# Adafruit_MacroPad_2040.net
KiCad netlist of a schematic drawn in EAGLE
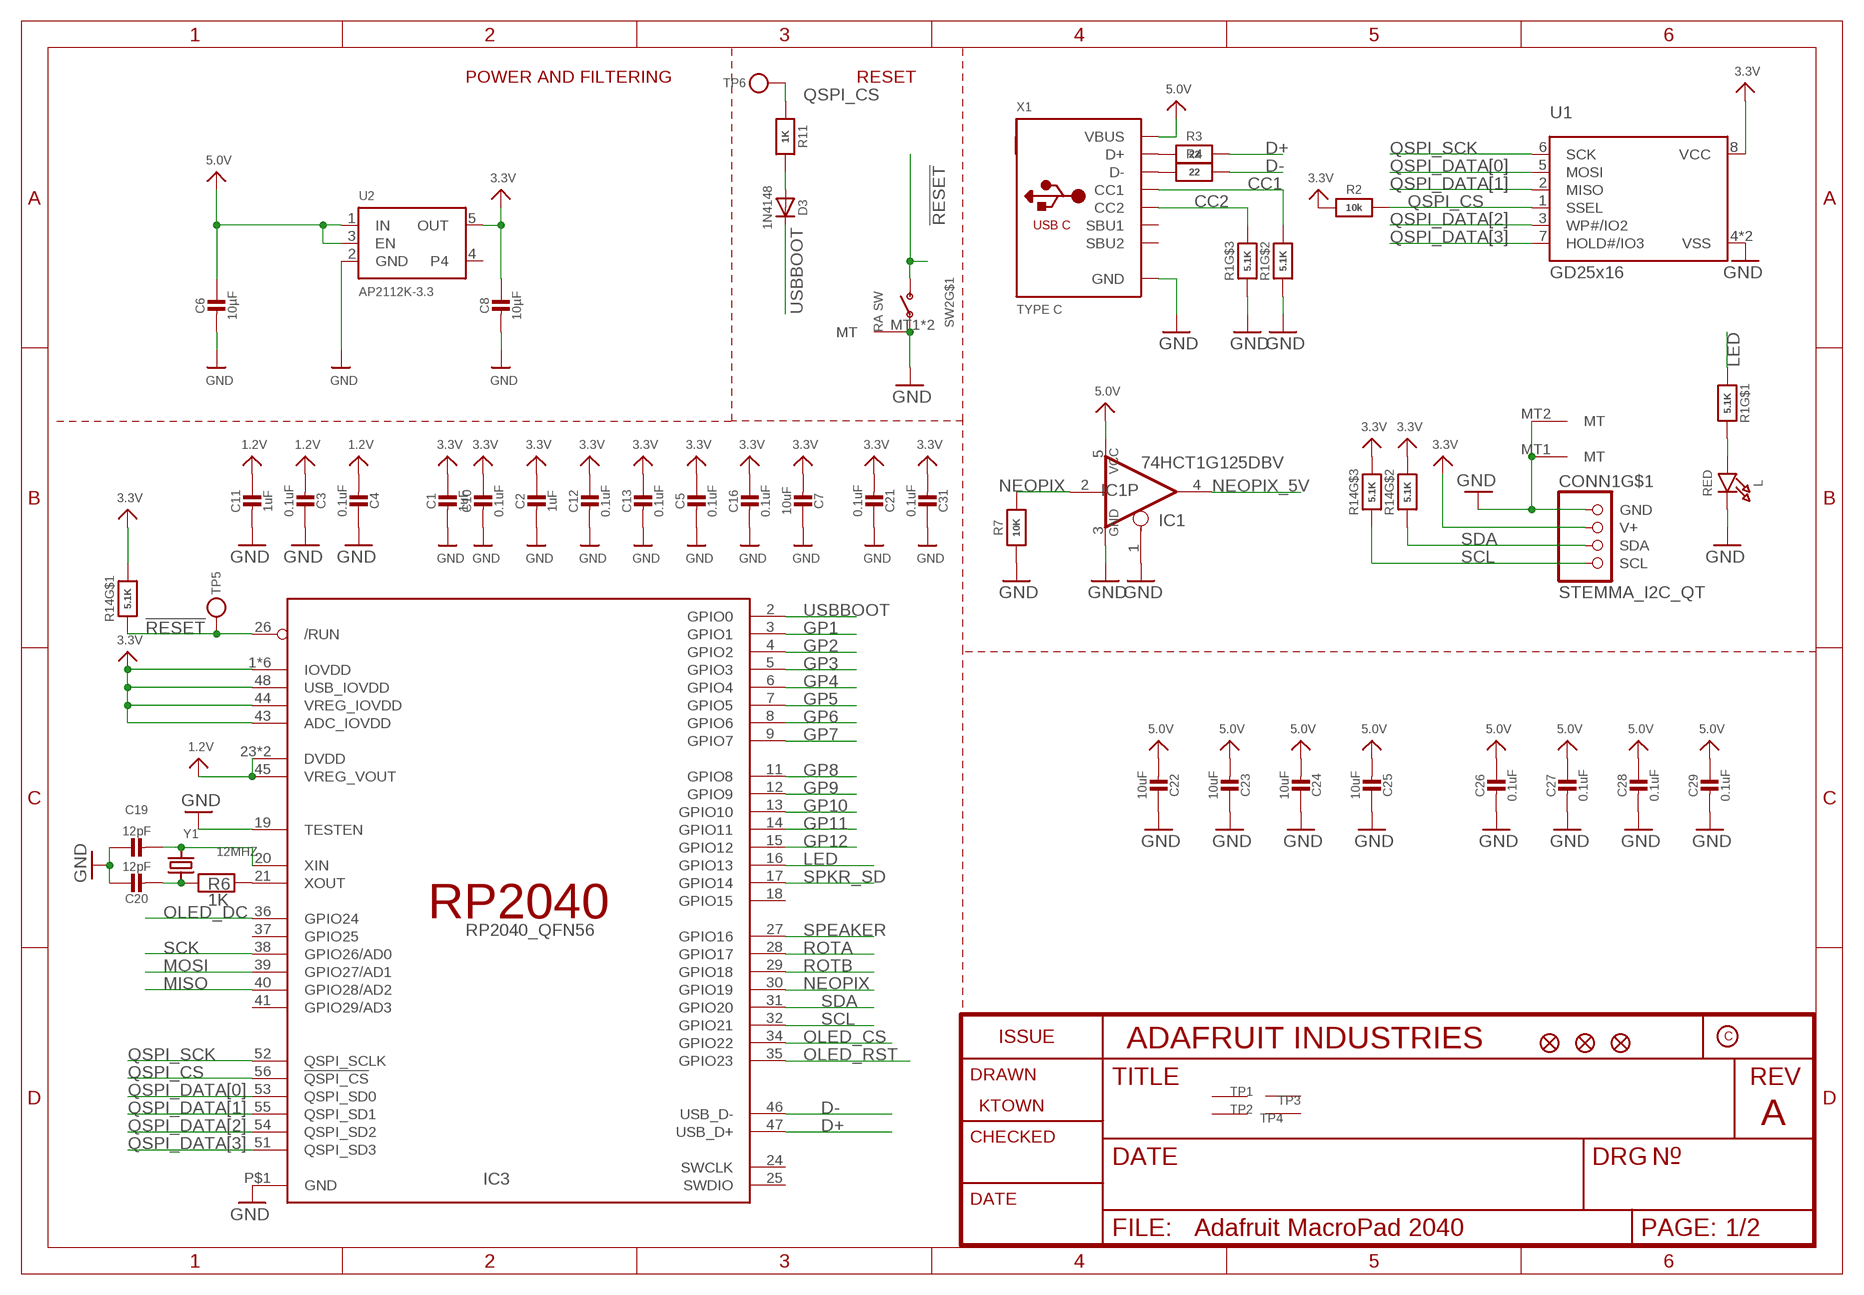
[diagram p0: schematic, sheet 1]
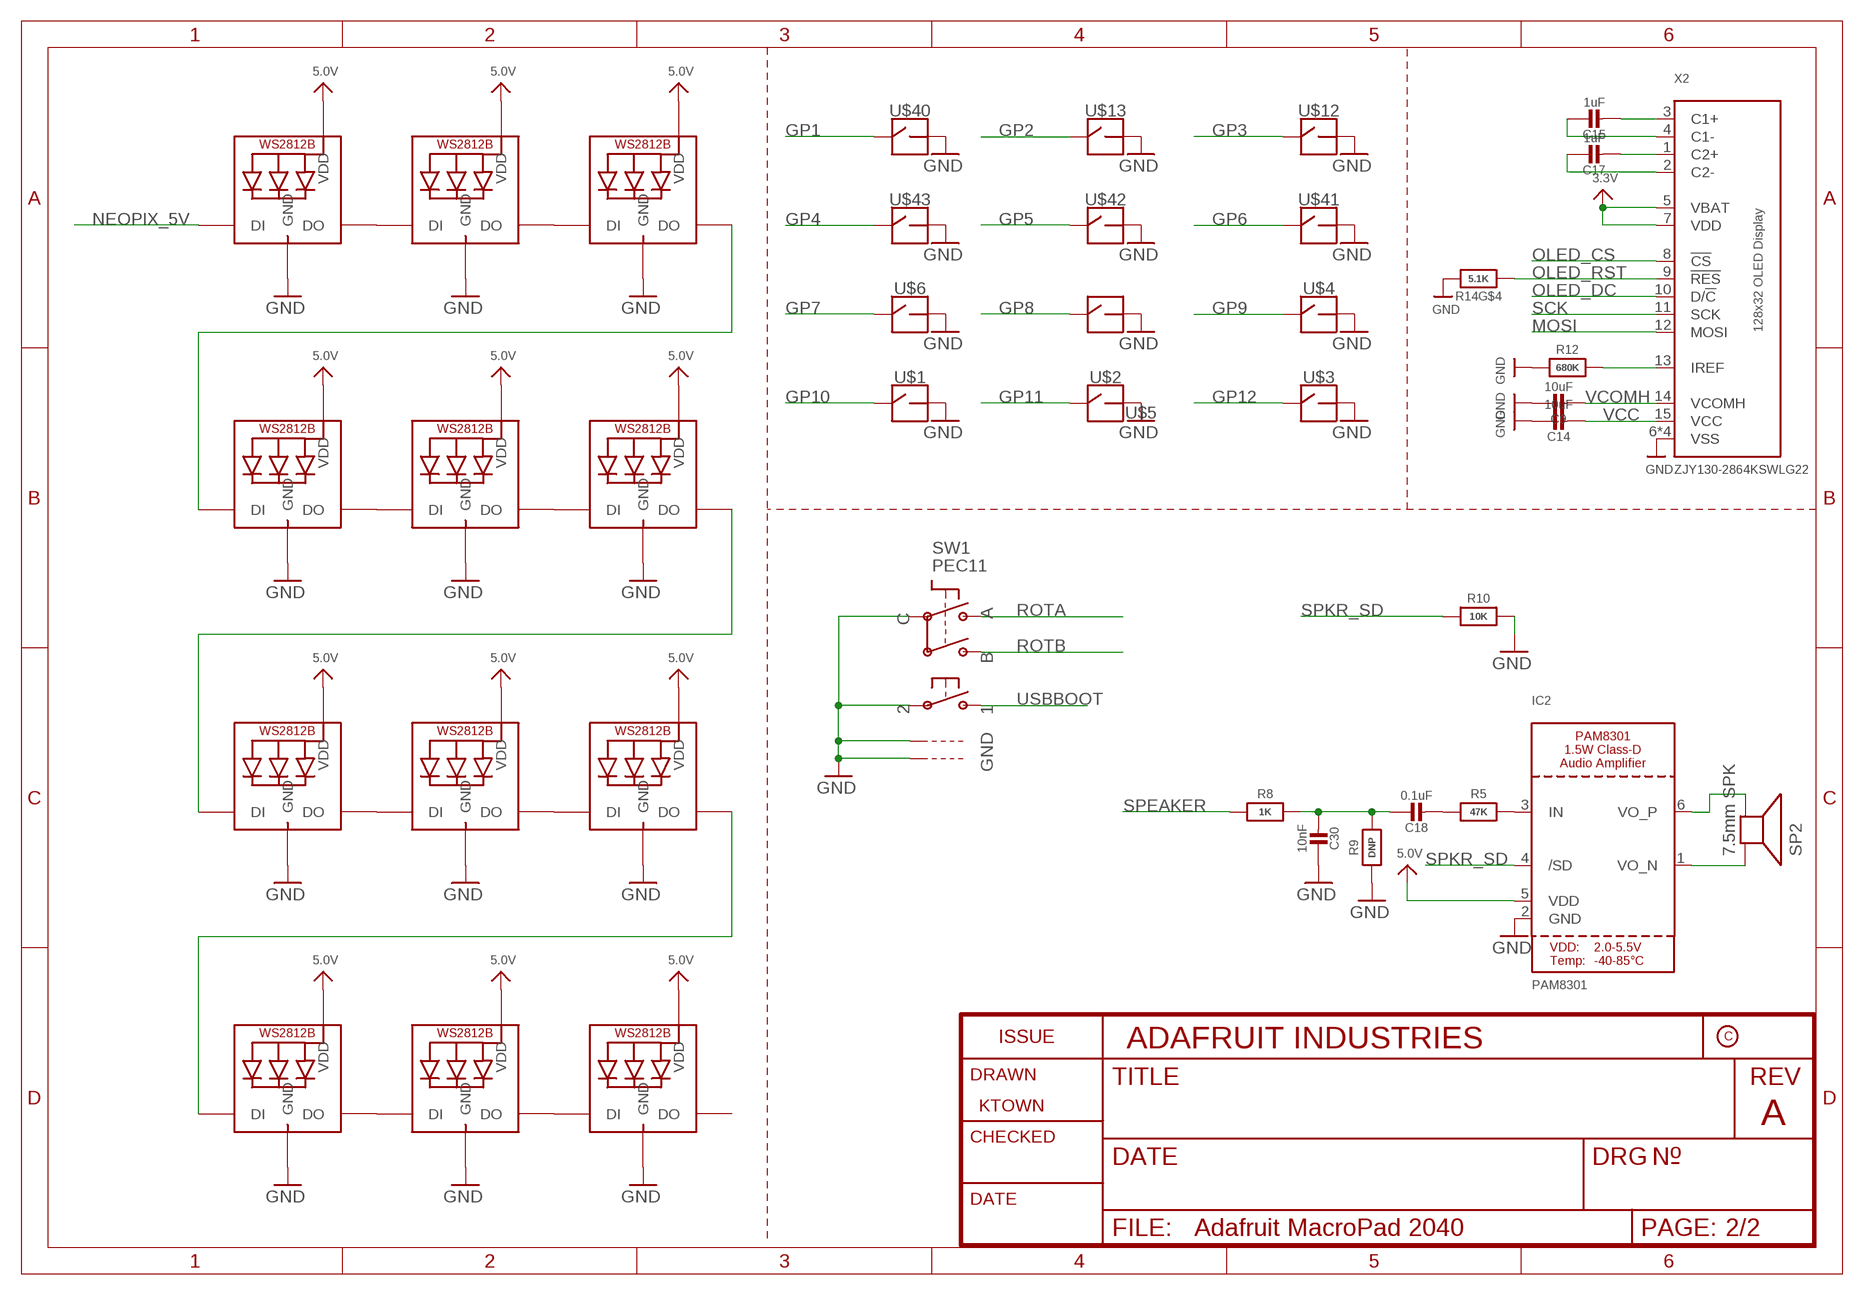
[diagram p1: schematic, sheet 2]

(export (version "E")
  (design (tool "Eeschema 10.0.6"))
  (components
    (comp (ref "C1")
      (value "1uF")
      (footprint "eagle-import:0603-NO")
      (libsource (lib "eagle-import") (part "CAP_CERAMIC0603_NO"))
    )
    (comp (ref "C2")
      (value "1uF")
      (footprint "eagle-import:0603-NO")
      (libsource (lib "eagle-import") (part "CAP_CERAMIC0603_NO"))
    )
    (comp (ref "C3")
      (value "0.1uF")
      (footprint "eagle-import:0603-NO")
      (libsource (lib "eagle-import") (part "CAP_CERAMIC0603_NO"))
    )
    (comp (ref "C4")
      (value "0.1uF")
      (footprint "eagle-import:0603-NO")
      (libsource (lib "eagle-import") (part "CAP_CERAMIC0603_NO"))
    )
    (comp (ref "C5")
      (value "0.1uF")
      (footprint "eagle-import:0603-NO")
      (libsource (lib "eagle-import") (part "CAP_CERAMIC0603_NO"))
    )
    (comp (ref "C6")
      (value "10µF")
      (footprint "eagle-import:0805-NO")
      (libsource (lib "eagle-import") (part "CAP_CERAMIC0805-NOOUTLINE"))
    )
    (comp (ref "C7")
      (value "10uF")
      (footprint "eagle-import:0805-NO")
      (libsource (lib "eagle-import") (part "CAP_CERAMIC0805-NOOUTLINE"))
    )
    (comp (ref "C8")
      (value "10µF")
      (footprint "eagle-import:0805-NO")
      (fields (field (name "REV") "C"))
      (libsource (lib "eagle-import") (part "CAP_CERAMIC0805-NOOUTLINE"))
    )
    (comp (ref "C10")
      (value "0.1uF")
      (footprint "eagle-import:0603-NO")
      (libsource (lib "eagle-import") (part "CAP_CERAMIC0603_NO"))
    )
    (comp (ref "C11")
      (value "1uF")
      (footprint "eagle-import:0603-NO")
      (libsource (lib "eagle-import") (part "CAP_CERAMIC0603_NO"))
    )
    (comp (ref "C12")
      (value "0.1uF")
      (footprint "eagle-import:0603-NO")
      (libsource (lib "eagle-import") (part "CAP_CERAMIC0603_NO"))
    )
    (comp (ref "C13")
      (value "0.1uF")
      (footprint "eagle-import:0603-NO")
      (libsource (lib "eagle-import") (part "CAP_CERAMIC0603_NO"))
    )
    (comp (ref "C16")
      (value "0.1uF")
      (footprint "eagle-import:0603-NO")
      (libsource (lib "eagle-import") (part "CAP_CERAMIC0603_NO"))
    )
    (comp (ref "C19")
      (value "12pF")
      (footprint "eagle-import:0603-NO")
      (libsource (lib "eagle-import") (part "CAP_CERAMIC0603_NO"))
    )
    (comp (ref "C20")
      (value "12pF")
      (footprint "eagle-import:0603-NO")
      (libsource (lib "eagle-import") (part "CAP_CERAMIC0603_NO"))
    )
    (comp (ref "C21")
      (value "0.1uF")
      (footprint "eagle-import:0603-NO")
      (libsource (lib "eagle-import") (part "CAP_CERAMIC0603_NO"))
    )
    (comp (ref "C22")
      (value "10uF")
      (footprint "eagle-import:0805-NO")
      (libsource (lib "eagle-import") (part "CAP_CERAMIC0805-NOOUTLINE"))
    )
    (comp (ref "C23")
      (value "10uF")
      (footprint "eagle-import:0805-NO")
      (libsource (lib "eagle-import") (part "CAP_CERAMIC0805-NOOUTLINE"))
    )
    (comp (ref "C24")
      (value "10uF")
      (footprint "eagle-import:0805-NO")
      (libsource (lib "eagle-import") (part "CAP_CERAMIC0805-NOOUTLINE"))
    )
    (comp (ref "C25")
      (value "10uF")
      (footprint "eagle-import:0805-NO")
      (libsource (lib "eagle-import") (part "CAP_CERAMIC0805-NOOUTLINE"))
    )
    (comp (ref "C26")
      (value "0.1uF")
      (footprint "eagle-import:0603-NO")
      (libsource (lib "eagle-import") (part "CAP_CERAMIC0603_NO"))
    )
    (comp (ref "C27")
      (value "0.1uF")
      (footprint "eagle-import:0603-NO")
      (libsource (lib "eagle-import") (part "CAP_CERAMIC0603_NO"))
    )
    (comp (ref "C28")
      (value "0.1uF")
      (footprint "eagle-import:0603-NO")
      (libsource (lib "eagle-import") (part "CAP_CERAMIC0603_NO"))
    )
    (comp (ref "C29")
      (value "0.1uF")
      (footprint "eagle-import:0603-NO")
      (libsource (lib "eagle-import") (part "CAP_CERAMIC0603_NO"))
    )
    (comp (ref "C31")
      (value "0.1uF")
      (footprint "eagle-import:0603-NO")
      (libsource (lib "eagle-import") (part "CAP_CERAMIC0603_NO"))
    )
    (comp (ref "CONN1")
      (value "STEMMA_I2C_QT")
      (footprint "eagle-import:JST_SH4")
      (libsource (lib "eagle-import") (part "STEMMA_I2C_QT"))
    )
    (comp (ref "D3")
      (value "1N4148")
      (footprint "eagle-import:SOD-323")
      (libsource (lib "eagle-import") (part "DIODESOD-323"))
    )
    (comp (ref "IC1")
      (value "74HCT1G125DBV")
      (footprint "eagle-import:SOT23-5")
      (libsource (lib "eagle-import") (part "741G125DBVAHC"))
    )
    (comp (ref "IC3")
      (value "RP2040_QFN56")
      (footprint "eagle-import:QFN56_7MM_REDUCEDEPAD")
      (libsource (lib "eagle-import") (part "RP2040_QFN56"))
    )
    (comp (ref "L")
      (value "RED")
      (footprint "eagle-import:CHIPLED_0603_NOOUTLINE")
      (libsource (lib "eagle-import") (part "LED0603_NOOUTLINE"))
    )
    (comp (ref "R1")
      (value "5.1K")
      (footprint "eagle-import:RESPACK_4X0603")
      (libsource (lib "eagle-import") (part "RESISTOR_4PACK"))
    )
    (comp (ref "R2")
      (value "10k")
      (footprint "eagle-import:0603-NO")
      (libsource (lib "eagle-import") (part "RESISTOR_0603_NOOUT"))
    )
    (comp (ref "R3")
      (value "22")
      (footprint "eagle-import:0603-NO")
      (libsource (lib "eagle-import") (part "RESISTOR_0603_NOOUT"))
    )
    (comp (ref "R4")
      (value "22")
      (footprint "eagle-import:0603-NO")
      (libsource (lib "eagle-import") (part "RESISTOR_0603_NOOUT"))
    )
    (comp (ref "R6")
      (value "1K")
      (footprint "eagle-import:0603-NO")
      (libsource (lib "eagle-import") (part "RESISTOR_0603_NOOUT"))
    )
    (comp (ref "R7")
      (value "10K")
      (footprint "eagle-import:0603-NO")
      (libsource (lib "eagle-import") (part "RESISTOR_0603_NOOUT"))
    )
    (comp (ref "R11")
      (value "1K")
      (footprint "eagle-import:0603-NO")
      (libsource (lib "eagle-import") (part "RESISTOR_0603_NOOUT"))
    )
    (comp (ref "R14")
      (value "5.1K")
      (footprint "eagle-import:RESPACK_4X0603")
      (libsource (lib "eagle-import") (part "RESISTOR_4PACK"))
    )
    (comp (ref "SW2")
      (value "RA SW")
      (footprint "eagle-import:SPST_TACTILE_RA")
      (libsource (lib "eagle-import") (part "SWITCH_SPST_TACT_RA"))
    )
    (comp (ref "TP1")
      (value "SEWTAP_SMTNUTM3")
      (footprint "eagle-import:SMT_NUT_3MM")
      (libsource (lib "eagle-import") (part "SEWTAP_SMTNUTM3"))
    )
    (comp (ref "TP2")
      (value "SEWTAP_SMTNUTM3")
      (footprint "eagle-import:SMT_NUT_3MM")
      (libsource (lib "eagle-import") (part "SEWTAP_SMTNUTM3"))
    )
    (comp (ref "TP3")
      (value "SEWTAP_SMTNUTM3")
      (footprint "eagle-import:SMT_NUT_3MM")
      (libsource (lib "eagle-import") (part "SEWTAP_SMTNUTM3"))
    )
    (comp (ref "TP4")
      (value "SEWTAP_SMTNUTM3")
      (footprint "eagle-import:SMT_NUT_3MM")
      (libsource (lib "eagle-import") (part "SEWTAP_SMTNUTM3"))
    )
    (comp (ref "TP5")
      (value "TESTPOINTROUND1.5MMNO")
      (footprint "eagle-import:TESTPOINT_ROUND_1.5MM_NO")
      (libsource (lib "eagle-import") (part "TESTPOINTROUND1.5MMNO"))
    )
    (comp (ref "TP6")
      (value "TESTPOINTROUND1.5MMNO")
      (footprint "eagle-import:TESTPOINT_ROUND_1.5MM_NO")
      (libsource (lib "eagle-import") (part "TESTPOINTROUND1.5MMNO"))
    )
    (comp (ref "U$34")
      (value "FIDUCIAL_1MM")
      (footprint "eagle-import:FIDUCIAL_1MM")
      (libsource (lib "eagle-import") (part "FIDUCIAL_1MM"))
    )
    (comp (ref "U$35")
      (value "FIDUCIAL_1MM")
      (footprint "eagle-import:FIDUCIAL_1MM")
      (libsource (lib "eagle-import") (part "FIDUCIAL_1MM"))
    )
    (comp (ref "U$80")
      (value "FIDUCIAL_1MM")
      (footprint "eagle-import:FIDUCIAL_1MM")
      (libsource (lib "eagle-import") (part "FIDUCIAL_1MM"))
    )
    (comp (ref "U1")
      (value "GD25x16")
      (footprint "eagle-import:USON8_4X4")
      (libsource (lib "eagle-import") (part "SPIFLASH_8PIN_4X4"))
    )
    (comp (ref "U2")
      (value "AP2112K-3.3")
      (footprint "eagle-import:SOT23-5")
      (libsource (lib "eagle-import") (part "VREG_SOT23-5"))
    )
    (comp (ref "X1")
      (value "TYPE C")
      (footprint "eagle-import:USB_C_CUSB31-CFM2AX-01-X")
      (libsource (lib "eagle-import") (part "USB_C"))
    )
    (comp (ref "Y1")
      (value "12MHZ")
      (footprint "eagle-import:CRYSTAL_2.5X2")
      (libsource (lib "eagle-import") (part "CRYSTAL2.5X2.0"))
    )
    (comp (ref "C9")
      (value "10uF")
      (footprint "eagle-import:0805-NO")
      (libsource (lib "eagle-import") (part "CAP_CERAMIC0805-NOOUTLINE"))
    )
    (comp (ref "C14")
      (value "10uF")
      (footprint "eagle-import:0805-NO")
      (libsource (lib "eagle-import") (part "CAP_CERAMIC0805-NOOUTLINE"))
    )
    (comp (ref "C15")
      (value "1uF")
      (footprint "eagle-import:0603-NO")
      (libsource (lib "eagle-import") (part "CAP_CERAMIC0603_NO"))
    )
    (comp (ref "C17")
      (value "1uF")
      (footprint "eagle-import:0603-NO")
      (libsource (lib "eagle-import") (part "CAP_CERAMIC0603_NO"))
    )
    (comp (ref "C18")
      (value "0.1uF")
      (footprint "eagle-import:0603-NO")
      (libsource (lib "eagle-import") (part "CAP_CERAMIC0603_NO"))
    )
    (comp (ref "C30")
      (value "10nF")
      (footprint "eagle-import:0603-NO")
      (libsource (lib "eagle-import") (part "CAP_CERAMIC0603_NO"))
    )
    (comp (ref "IC2")
      (value "PAM8301")
      (footprint "eagle-import:SOT23-6")
      (libsource (lib "eagle-import") (part "PAM8301"))
    )
    (comp (ref "LED1")
      (value "WS2812B_SK6812E")
      (footprint "eagle-import:NEO3535_REVERSE")
      (libsource (lib "eagle-import") (part "WS2812B_SK6812E"))
    )
    (comp (ref "LED2")
      (value "WS2812B_SK6812E")
      (footprint "eagle-import:NEO3535_REVERSE")
      (libsource (lib "eagle-import") (part "WS2812B_SK6812E"))
    )
    (comp (ref "LED3")
      (value "WS2812B_SK6812E")
      (footprint "eagle-import:NEO3535_REVERSE")
      (libsource (lib "eagle-import") (part "WS2812B_SK6812E"))
    )
    (comp (ref "LED4")
      (value "WS2812B_SK6812E")
      (footprint "eagle-import:NEO3535_REVERSE")
      (libsource (lib "eagle-import") (part "WS2812B_SK6812E"))
    )
    (comp (ref "LED5")
      (value "WS2812B_SK6812E")
      (footprint "eagle-import:NEO3535_REVERSE")
      (libsource (lib "eagle-import") (part "WS2812B_SK6812E"))
    )
    (comp (ref "LED6")
      (value "WS2812B_SK6812E")
      (footprint "eagle-import:NEO3535_REVERSE")
      (libsource (lib "eagle-import") (part "WS2812B_SK6812E"))
    )
    (comp (ref "LED7")
      (value "WS2812B_SK6812E")
      (footprint "eagle-import:NEO3535_REVERSE")
      (libsource (lib "eagle-import") (part "WS2812B_SK6812E"))
    )
    (comp (ref "LED8")
      (value "WS2812B_SK6812E")
      (footprint "eagle-import:NEO3535_REVERSE")
      (libsource (lib "eagle-import") (part "WS2812B_SK6812E"))
    )
    (comp (ref "LED9")
      (value "WS2812B_SK6812E")
      (footprint "eagle-import:NEO3535_REVERSE")
      (libsource (lib "eagle-import") (part "WS2812B_SK6812E"))
    )
    (comp (ref "LED10")
      (value "WS2812B_SK6812E")
      (footprint "eagle-import:NEO3535_REVERSE")
      (libsource (lib "eagle-import") (part "WS2812B_SK6812E"))
    )
    (comp (ref "LED11")
      (value "WS2812B_SK6812E")
      (footprint "eagle-import:NEO3535_REVERSE")
      (libsource (lib "eagle-import") (part "WS2812B_SK6812E"))
    )
    (comp (ref "LED12")
      (value "WS2812B_SK6812E")
      (footprint "eagle-import:NEO3535_REVERSE")
      (libsource (lib "eagle-import") (part "WS2812B_SK6812E"))
    )
    (comp (ref "R5")
      (value "47K")
      (footprint "eagle-import:0603-NO")
      (libsource (lib "eagle-import") (part "RESISTOR_0603_NOOUT"))
    )
    (comp (ref "R8")
      (value "1K")
      (footprint "eagle-import:0603-NO")
      (libsource (lib "eagle-import") (part "RESISTOR_0603_NOOUT"))
    )
    (comp (ref "R9")
      (value "DNP")
      (footprint "eagle-import:0603-NO")
      (libsource (lib "eagle-import") (part "RESISTOR_0603_NOOUT"))
    )
    (comp (ref "R10")
      (value "10K")
      (footprint "eagle-import:0603-NO")
      (libsource (lib "eagle-import") (part "RESISTOR_0603_NOOUT"))
    )
    (comp (ref "R12")
      (value "680K")
      (footprint "eagle-import:0603-NO")
      (libsource (lib "eagle-import") (part "RESISTOR_0603_NOOUT"))
    )
    (comp (ref "SP2")
      (value "7.5mm SPK")
      (footprint "eagle-import:BUZZER_SMT_7.5MM")
      (libsource (lib "eagle-import") (part "SPEAKER_7.5MM"))
    )
    (comp (ref "SW1")
      (value "PEC11")
      (footprint "eagle-import:PEC11+SWITCH")
      (libsource (lib "eagle-import") (part "ENCODER_PLUS_SWITCH_PEC11_BOURNS"))
    )
    (comp (ref "U$1")
      (value "SOCKET")
      (footprint "eagle-import:KAILH_SOCKET")
      (libsource (lib "eagle-import") (part "KBD_SWITCH_KAILH_SOCKETBOX_JADE_KAILH_SOCKET"))
    )
    (comp (ref "U$2")
      (value "SOCKET")
      (footprint "eagle-import:KAILH_SOCKET")
      (libsource (lib "eagle-import") (part "KBD_SWITCH_KAILH_SOCKETBOX_JADE_KAILH_SOCKET"))
    )
    (comp (ref "U$3")
      (value "SOCKET")
      (footprint "eagle-import:KAILH_SOCKET")
      (libsource (lib "eagle-import") (part "KBD_SWITCH_KAILH_SOCKETBOX_JADE_KAILH_SOCKET"))
    )
    (comp (ref "U$4")
      (value "SOCKET")
      (footprint "eagle-import:KAILH_SOCKET")
      (libsource (lib "eagle-import") (part "KBD_SWITCH_KAILH_SOCKETBOX_JADE_KAILH_SOCKET"))
    )
    (comp (ref "U$5")
      (value "SOCKET")
      (footprint "eagle-import:KAILH_SOCKET")
      (libsource (lib "eagle-import") (part "KBD_SWITCH_KAILH_SOCKETBOX_JADE_KAILH_SOCKET"))
    )
    (comp (ref "U$6")
      (value "SOCKET")
      (footprint "eagle-import:KAILH_SOCKET")
      (libsource (lib "eagle-import") (part "KBD_SWITCH_KAILH_SOCKETBOX_JADE_KAILH_SOCKET"))
    )
    (comp (ref "U$12")
      (value "SOCKET")
      (footprint "eagle-import:KAILH_SOCKET")
      (libsource (lib "eagle-import") (part "KBD_SWITCH_KAILH_SOCKETBOX_JADE_KAILH_SOCKET"))
    )
    (comp (ref "U$13")
      (value "SOCKET")
      (footprint "eagle-import:KAILH_SOCKET")
      (libsource (lib "eagle-import") (part "KBD_SWITCH_KAILH_SOCKETBOX_JADE_KAILH_SOCKET"))
    )
    (comp (ref "U$40")
      (value "SOCKET")
      (footprint "eagle-import:KAILH_SOCKET")
      (libsource (lib "eagle-import") (part "KBD_SWITCH_KAILH_SOCKETBOX_JADE_KAILH_SOCKET"))
    )
    (comp (ref "U$41")
      (value "SOCKET")
      (footprint "eagle-import:KAILH_SOCKET")
      (libsource (lib "eagle-import") (part "KBD_SWITCH_KAILH_SOCKETBOX_JADE_KAILH_SOCKET"))
    )
    (comp (ref "U$42")
      (value "SOCKET")
      (footprint "eagle-import:KAILH_SOCKET")
      (libsource (lib "eagle-import") (part "KBD_SWITCH_KAILH_SOCKETBOX_JADE_KAILH_SOCKET"))
    )
    (comp (ref "U$43")
      (value "SOCKET")
      (footprint "eagle-import:KAILH_SOCKET")
      (libsource (lib "eagle-import") (part "KBD_SWITCH_KAILH_SOCKETBOX_JADE_KAILH_SOCKET"))
    )
    (comp (ref "X2")
      (value "ZJY130-2864KSWLG22")
      (footprint "eagle-import:ZJY130-2864KSWLG22")
      (libsource (lib "eagle-import") (part "ZJY130-2864KSWLG22"))
    )
  )
  (nets
    (net (code "1") (name "1.2V") (class "Default")
      (node (ref "C11") (pin "1") (pinfunction "1_1") (pintype "passive"))
      (node (ref "C3") (pin "2") (pinfunction "2_2") (pintype "passive"))
      (node (ref "C4") (pin "2") (pinfunction "2_2") (pintype "passive"))
      (node (ref "IC3") (pin "23") (pinfunction "DVDD_23") (pintype "power_in"))
      (node (ref "IC3") (pin "45") (pinfunction "VREG_VOUT_45") (pintype "power_in"))
      (node (ref "IC3") (pin "50") (pinfunction "DVDD_50") (pintype "power_in"))
    )
    (net (code "2") (name "3.3V") (class "Default")
      (node (ref "C1") (pin "1") (pinfunction "1_1") (pintype "passive"))
      (node (ref "C10") (pin "1") (pinfunction "1_1") (pintype "passive"))
      (node (ref "C12") (pin "1") (pinfunction "1_1") (pintype "passive"))
      (node (ref "C13") (pin "1") (pinfunction "1_1") (pintype "passive"))
      (node (ref "C16") (pin "1") (pinfunction "1_1") (pintype "passive"))
      (node (ref "C2") (pin "1") (pinfunction "1_1") (pintype "passive"))
      (node (ref "C21") (pin "2") (pinfunction "2_2") (pintype "passive"))
      (node (ref "C31") (pin "2") (pinfunction "2_2") (pintype "passive"))
      (node (ref "C5") (pin "1") (pinfunction "1_1") (pintype "passive"))
      (node (ref "C7") (pin "2") (pinfunction "2_2") (pintype "passive"))
      (node (ref "C8") (pin "1") (pinfunction "1_1") (pintype "passive"))
      (node (ref "CONN1") (pin "2") (pinfunction "V+_2") (pintype "passive"))
      (node (ref "IC3") (pin "1") (pinfunction "IOVDD_1") (pintype "power_in"))
      (node (ref "IC3") (pin "10") (pinfunction "IOVDD_10") (pintype "power_in"))
      (node (ref "IC3") (pin "22") (pinfunction "IOVDD_22") (pintype "power_in"))
      (node (ref "IC3") (pin "33") (pinfunction "IOVDD_33") (pintype "power_in"))
      (node (ref "IC3") (pin "42") (pinfunction "IOVDD_42") (pintype "power_in"))
      (node (ref "IC3") (pin "43") (pinfunction "ADC_IOVDD_43") (pintype "power_in"))
      (node (ref "IC3") (pin "44") (pinfunction "VREG_IOVDD_44") (pintype "power_in"))
      (node (ref "IC3") (pin "48") (pinfunction "USB_IOVDD_48") (pintype "power_in"))
      (node (ref "IC3") (pin "49") (pinfunction "IOVDD_49") (pintype "power_in"))
      (node (ref "R14") (pin "6") (pinfunction "2_6") (pintype "passive"))
      (node (ref "R14") (pin "7") (pinfunction "2_7") (pintype "passive"))
      (node (ref "R14") (pin "8") (pinfunction "2_8") (pintype "passive"))
      (node (ref "R2") (pin "1") (pinfunction "1_1") (pintype "passive"))
      (node (ref "U1") (pin "8") (pinfunction "VCC_8") (pintype "bidirectional"))
      (node (ref "U2") (pin "5") (pinfunction "OUT_5") (pintype "power_in"))
      (node (ref "X2") (pin "5") (pinfunction "VBAT_5") (pintype "power_in"))
      (node (ref "X2") (pin "7") (pinfunction "VDD_7") (pintype "power_in"))
    )
    (net (code "3") (name "5.0V") (class "Default")
      (node (ref "C22") (pin "2") (pinfunction "2_2") (pintype "passive"))
      (node (ref "C23") (pin "2") (pinfunction "2_2") (pintype "passive"))
      (node (ref "C24") (pin "2") (pinfunction "2_2") (pintype "passive"))
      (node (ref "C25") (pin "2") (pinfunction "2_2") (pintype "passive"))
      (node (ref "C26") (pin "1") (pinfunction "1_1") (pintype "passive"))
      (node (ref "C27") (pin "1") (pinfunction "1_1") (pintype "passive"))
      (node (ref "C28") (pin "1") (pinfunction "1_1") (pintype "passive"))
      (node (ref "C29") (pin "1") (pinfunction "1_1") (pintype "passive"))
      (node (ref "C6") (pin "1") (pinfunction "1_1") (pintype "passive"))
      (node (ref "IC1") (pin "5") (pinfunction "VCC_5") (pintype "power_in"))
      (node (ref "IC2") (pin "5") (pinfunction "VDD_5") (pintype "power_in"))
      (node (ref "LED1") (pin "1-VDD") (pinfunction "VDD_1-VDD") (pintype "power_in"))
      (node (ref "LED10") (pin "1-VDD") (pinfunction "VDD_1-VDD") (pintype "power_in"))
      (node (ref "LED11") (pin "1-VDD") (pinfunction "VDD_1-VDD") (pintype "power_in"))
      (node (ref "LED12") (pin "1-VDD") (pinfunction "VDD_1-VDD") (pintype "power_in"))
      (node (ref "LED2") (pin "1-VDD") (pinfunction "VDD_1-VDD") (pintype "power_in"))
      (node (ref "LED3") (pin "1-VDD") (pinfunction "VDD_1-VDD") (pintype "power_in"))
      (node (ref "LED4") (pin "1-VDD") (pinfunction "VDD_1-VDD") (pintype "power_in"))
      (node (ref "LED5") (pin "1-VDD") (pinfunction "VDD_1-VDD") (pintype "power_in"))
      (node (ref "LED6") (pin "1-VDD") (pinfunction "VDD_1-VDD") (pintype "power_in"))
      (node (ref "LED7") (pin "1-VDD") (pinfunction "VDD_1-VDD") (pintype "power_in"))
      (node (ref "LED8") (pin "1-VDD") (pinfunction "VDD_1-VDD") (pintype "power_in"))
      (node (ref "LED9") (pin "1-VDD") (pinfunction "VDD_1-VDD") (pintype "power_in"))
      (node (ref "U2") (pin "1") (pinfunction "IN_1") (pintype "power_in"))
      (node (ref "U2") (pin "3") (pinfunction "EN_3") (pintype "input"))
      (node (ref "X1") (pin "A4B9") (pinfunction "VBUS_A4B9") (pintype "power_in"))
      (node (ref "X1") (pin "B4A9") (pinfunction "VBUS_B4A9") (pintype "power_in"))
    )
    (net (code "4") (name "CC1") (class "Default")
      (node (ref "R1") (pin "7") (pinfunction "2_7") (pintype "passive"))
      (node (ref "X1") (pin "A5") (pinfunction "CC1_A5") (pintype "bidirectional"))
    )
    (net (code "5") (name "CC2") (class "Default")
      (node (ref "R1") (pin "6") (pinfunction "2_6") (pintype "passive"))
      (node (ref "X1") (pin "B5") (pinfunction "CC2_B5") (pintype "bidirectional"))
    )
    (net (code "6") (name "D+") (class "Default")
      (node (ref "IC3") (pin "47") (pinfunction "USB_D+_47") (pintype "bidirectional"))
      (node (ref "R3") (pin "2") (pinfunction "2_2") (pintype "passive"))
    )
    (net (code "7") (name "D-") (class "Default")
      (node (ref "IC3") (pin "46") (pinfunction "USB_D-_46") (pintype "bidirectional"))
      (node (ref "R4") (pin "2") (pinfunction "2_2") (pintype "passive"))
    )
    (net (code "8") (name "GND") (class "Default")
      (node (ref "C1") (pin "2") (pinfunction "2_2") (pintype "passive"))
      (node (ref "C10") (pin "2") (pinfunction "2_2") (pintype "passive"))
      (node (ref "C11") (pin "2") (pinfunction "2_2") (pintype "passive"))
      (node (ref "C12") (pin "2") (pinfunction "2_2") (pintype "passive"))
      (node (ref "C13") (pin "2") (pinfunction "2_2") (pintype "passive"))
      (node (ref "C14") (pin "1") (pinfunction "1_1") (pintype "passive"))
      (node (ref "C16") (pin "2") (pinfunction "2_2") (pintype "passive"))
      (node (ref "C19") (pin "1") (pinfunction "1_1") (pintype "passive"))
      (node (ref "C2") (pin "2") (pinfunction "2_2") (pintype "passive"))
      (node (ref "C20") (pin "1") (pinfunction "1_1") (pintype "passive"))
      (node (ref "C21") (pin "1") (pinfunction "1_1") (pintype "passive"))
      (node (ref "C22") (pin "1") (pinfunction "1_1") (pintype "passive"))
      (node (ref "C23") (pin "1") (pinfunction "1_1") (pintype "passive"))
      (node (ref "C24") (pin "1") (pinfunction "1_1") (pintype "passive"))
      (node (ref "C25") (pin "1") (pinfunction "1_1") (pintype "passive"))
      (node (ref "C26") (pin "2") (pinfunction "2_2") (pintype "passive"))
      (node (ref "C27") (pin "2") (pinfunction "2_2") (pintype "passive"))
      (node (ref "C28") (pin "2") (pinfunction "2_2") (pintype "passive"))
      (node (ref "C29") (pin "2") (pinfunction "2_2") (pintype "passive"))
      (node (ref "C3") (pin "1") (pinfunction "1_1") (pintype "passive"))
      (node (ref "C30") (pin "1") (pinfunction "1_1") (pintype "passive"))
      (node (ref "C31") (pin "1") (pinfunction "1_1") (pintype "passive"))
      (node (ref "C4") (pin "1") (pinfunction "1_1") (pintype "passive"))
      (node (ref "C5") (pin "2") (pinfunction "2_2") (pintype "passive"))
      (node (ref "C6") (pin "2") (pinfunction "2_2") (pintype "passive"))
      (node (ref "C7") (pin "1") (pinfunction "1_1") (pintype "passive"))
      (node (ref "C8") (pin "2") (pinfunction "2_2") (pintype "passive"))
      (node (ref "C9") (pin "1") (pinfunction "1_1") (pintype "passive"))
      (node (ref "CONN1") (pin "1") (pinfunction "GND_1") (pintype "passive"))
      (node (ref "CONN1") (pin "MT1") (pinfunction "MT_MT1") (pintype "bidirectional"))
      (node (ref "CONN1") (pin "MT2") (pinfunction "MT_MT2") (pintype "bidirectional"))
      (node (ref "IC1") (pin "1") (pinfunction "OE_1") (pintype "input"))
      (node (ref "IC1") (pin "3") (pinfunction "GND_3") (pintype "power_in"))
      (node (ref "IC2") (pin "2") (pinfunction "GND_2") (pintype "power_in"))
      (node (ref "IC3") (pin "19") (pinfunction "TESTEN_19") (pintype "input"))
      (node (ref "IC3") (pin "P$1") (pinfunction "GND_P$1") (pintype "power_in"))
      (node (ref "L") (pin "C") (pinfunction "C_C") (pintype "passive"))
      (node (ref "LED1") (pin "3-GND") (pinfunction "GND_3-GND") (pintype "power_in"))
      (node (ref "LED10") (pin "3-GND") (pinfunction "GND_3-GND") (pintype "power_in"))
      (node (ref "LED11") (pin "3-GND") (pinfunction "GND_3-GND") (pintype "power_in"))
      (node (ref "LED12") (pin "3-GND") (pinfunction "GND_3-GND") (pintype "power_in"))
      (node (ref "LED2") (pin "3-GND") (pinfunction "GND_3-GND") (pintype "power_in"))
      (node (ref "LED3") (pin "3-GND") (pinfunction "GND_3-GND") (pintype "power_in"))
      (node (ref "LED4") (pin "3-GND") (pinfunction "GND_3-GND") (pintype "power_in"))
      (node (ref "LED5") (pin "3-GND") (pinfunction "GND_3-GND") (pintype "power_in"))
      (node (ref "LED6") (pin "3-GND") (pinfunction "GND_3-GND") (pintype "power_in"))
      (node (ref "LED7") (pin "3-GND") (pinfunction "GND_3-GND") (pintype "power_in"))
      (node (ref "LED8") (pin "3-GND") (pinfunction "GND_3-GND") (pintype "power_in"))
      (node (ref "LED9") (pin "3-GND") (pinfunction "GND_3-GND") (pintype "power_in"))
      (node (ref "R1") (pin "2") (pinfunction "1_2") (pintype "passive"))
      (node (ref "R1") (pin "3") (pinfunction "1_3") (pintype "passive"))
      (node (ref "R10") (pin "2") (pinfunction "2_2") (pintype "passive"))
      (node (ref "R12") (pin "1") (pinfunction "1_1") (pintype "passive"))
      (node (ref "R14") (pin "5") (pinfunction "2_5") (pintype "passive"))
      (node (ref "R7") (pin "1") (pinfunction "1_1") (pintype "passive"))
      (node (ref "R9") (pin "1") (pinfunction "1_1") (pintype "passive"))
      (node (ref "SW1") (pin "P$2") (pinfunction "P$2_P$2") (pintype "passive"))
      (node (ref "SW1") (pin "P$C") (pinfunction "P$C_P$C") (pintype "passive"))
      (node (ref "SW1") (pin "P$GND1") (pinfunction "P$GND1_P$GND1") (pintype "passive"))
      (node (ref "SW1") (pin "P$GND2") (pinfunction "P$GND2_P$GND2") (pintype "passive"))
      (node (ref "SW2") (pin "1") (pinfunction "P_1") (pintype "passive"))
      (node (ref "SW2") (pin "MT1") (pinfunction "MT_MT1") (pintype "bidirectional"))
      (node (ref "SW2") (pin "MT2") (pinfunction "MT_MT2") (pintype "bidirectional"))
      (node (ref "U$1") (pin "2") (pinfunction "2_2") (pintype "passive"))
      (node (ref "U$12") (pin "2") (pinfunction "2_2") (pintype "passive"))
      (node (ref "U$13") (pin "2") (pinfunction "2_2") (pintype "passive"))
      (node (ref "U$2") (pin "2") (pinfunction "2_2") (pintype "passive"))
      (node (ref "U$3") (pin "2") (pinfunction "2_2") (pintype "passive"))
      (node (ref "U$4") (pin "2") (pinfunction "2_2") (pintype "passive"))
      (node (ref "U$40") (pin "2") (pinfunction "2_2") (pintype "passive"))
      (node (ref "U$41") (pin "2") (pinfunction "2_2") (pintype "passive"))
      (node (ref "U$42") (pin "2") (pinfunction "2_2") (pintype "passive"))
      (node (ref "U$43") (pin "2") (pinfunction "2_2") (pintype "passive"))
      (node (ref "U$5") (pin "2") (pinfunction "2_2") (pintype "passive"))
      (node (ref "U$6") (pin "2") (pinfunction "2_2") (pintype "passive"))
      (node (ref "U1") (pin "4") (pinfunction "VSS_4") (pintype "bidirectional"))
      (node (ref "U1") (pin "PAD") (pinfunction "VSS_PAD") (pintype "bidirectional"))
      (node (ref "U2") (pin "2") (pinfunction "GND_2") (pintype "power_in"))
      (node (ref "X1") (pin "A1B12") (pinfunction "GND_A1B12") (pintype "power_in"))
      (node (ref "X1") (pin "B1A12") (pinfunction "GND_B1A12") (pintype "power_in"))
      (node (ref "X2") (pin "16") (pinfunction "VSS_16") (pintype "power_in"))
      (node (ref "X2") (pin "6") (pinfunction "VSS_6") (pintype "power_in"))
      (node (ref "X2") (pin "SUPPORT1") (pinfunction "VSS_SUPPORT1") (pintype "power_in"))
      (node (ref "X2") (pin "SUPPORT2") (pinfunction "VSS_SUPPORT2") (pintype "power_in"))
    )
    (net (code "9") (name "GP1") (class "Default")
      (node (ref "IC3") (pin "3") (pinfunction "GPIO1_3") (pintype "bidirectional"))
      (node (ref "U$40") (pin "1") (pinfunction "1_1") (pintype "passive"))
    )
    (net (code "10") (name "GP2") (class "Default")
      (node (ref "IC3") (pin "4") (pinfunction "GPIO2_4") (pintype "bidirectional"))
      (node (ref "U$13") (pin "1") (pinfunction "1_1") (pintype "passive"))
    )
    (net (code "11") (name "GP3") (class "Default")
      (node (ref "IC3") (pin "5") (pinfunction "GPIO3_5") (pintype "bidirectional"))
      (node (ref "U$12") (pin "1") (pinfunction "1_1") (pintype "passive"))
    )
    (net (code "12") (name "GP4") (class "Default")
      (node (ref "IC3") (pin "6") (pinfunction "GPIO4_6") (pintype "bidirectional"))
      (node (ref "U$43") (pin "1") (pinfunction "1_1") (pintype "passive"))
    )
    (net (code "13") (name "GP5") (class "Default")
      (node (ref "IC3") (pin "7") (pinfunction "GPIO5_7") (pintype "bidirectional"))
      (node (ref "U$42") (pin "1") (pinfunction "1_1") (pintype "passive"))
    )
    (net (code "14") (name "GP6") (class "Default")
      (node (ref "IC3") (pin "8") (pinfunction "GPIO6_8") (pintype "bidirectional"))
      (node (ref "U$41") (pin "1") (pinfunction "1_1") (pintype "passive"))
    )
    (net (code "15") (name "GP7") (class "Default")
      (node (ref "IC3") (pin "9") (pinfunction "GPIO7_9") (pintype "bidirectional"))
      (node (ref "U$6") (pin "1") (pinfunction "1_1") (pintype "passive"))
    )
    (net (code "16") (name "GP8") (class "Default")
      (node (ref "IC3") (pin "11") (pinfunction "GPIO8_11") (pintype "bidirectional"))
      (node (ref "U$5") (pin "1") (pinfunction "1_1") (pintype "passive"))
    )
    (net (code "17") (name "GP9") (class "Default")
      (node (ref "IC3") (pin "12") (pinfunction "GPIO9_12") (pintype "bidirectional"))
      (node (ref "U$4") (pin "1") (pinfunction "1_1") (pintype "passive"))
    )
    (net (code "18") (name "GP10") (class "Default")
      (node (ref "IC3") (pin "13") (pinfunction "GPIO10_13") (pintype "bidirectional"))
      (node (ref "U$1") (pin "1") (pinfunction "1_1") (pintype "passive"))
    )
    (net (code "19") (name "GP11") (class "Default")
      (node (ref "IC3") (pin "14") (pinfunction "GPIO11_14") (pintype "bidirectional"))
      (node (ref "U$2") (pin "1") (pinfunction "1_1") (pintype "passive"))
    )
    (net (code "20") (name "GP12") (class "Default")
      (node (ref "IC3") (pin "15") (pinfunction "GPIO12_15") (pintype "bidirectional"))
      (node (ref "U$3") (pin "1") (pinfunction "1_1") (pintype "passive"))
    )
    (net (code "21") (name "LED") (class "Default")
      (node (ref "IC3") (pin "16") (pinfunction "GPIO13_16") (pintype "bidirectional"))
      (node (ref "R1") (pin "1") (pinfunction "1_1") (pintype "passive"))
    )
    (net (code "22") (name "MISO") (class "Default")
      (node (ref "IC3") (pin "40") (pinfunction "GPIO28/AD2_40") (pintype "bidirectional"))
    )
    (net (code "23") (name "MOSI") (class "Default")
      (node (ref "IC3") (pin "39") (pinfunction "GPIO27/AD1_39") (pintype "bidirectional"))
      (node (ref "X2") (pin "12") (pinfunction "MOSI_12") (pintype "input"))
    )
    (net (code "24") (name "NEOPIX") (class "Default")
      (node (ref "IC1") (pin "2") (pinfunction "I_2") (pintype "input"))
      (node (ref "IC3") (pin "30") (pinfunction "GPIO19_30") (pintype "bidirectional"))
      (node (ref "R7") (pin "2") (pinfunction "2_2") (pintype "passive"))
    )
    (net (code "25") (name "NEOPIX_5V") (class "Default")
      (node (ref "IC1") (pin "4") (pinfunction "O_4") (pintype "tri_state"))
      (node (ref "LED1") (pin "4-DIN") (pinfunction "DI_4-DIN") (pintype "input"))
    )
    (net (code "26") (name "Net-(C18-Pad1)") (class "Default")
      (node (ref "C18") (pin "1") (pinfunction "1_1") (pintype "passive"))
      (node (ref "C30") (pin "2") (pinfunction "2_2") (pintype "passive"))
      (node (ref "R8") (pin "2") (pinfunction "2_2") (pintype "passive"))
      (node (ref "R9") (pin "2") (pinfunction "2_2") (pintype "passive"))
    )
    (net (code "27") (name "Net-(C18-Pad2)") (class "Default")
      (node (ref "C18") (pin "2") (pinfunction "2_2") (pintype "passive"))
      (node (ref "R5") (pin "1") (pinfunction "1_1") (pintype "passive"))
    )
    (net (code "28") (name "Net-(C20-Pad2)") (class "Default")
      (node (ref "C20") (pin "2") (pinfunction "2_2") (pintype "passive"))
      (node (ref "R6") (pin "1") (pinfunction "1_1") (pintype "passive"))
      (node (ref "Y1") (pin "1") (pinfunction "1_1") (pintype "passive"))
    )
    (net (code "29") (name "Net-(D3-PadA)") (class "Default")
      (node (ref "D3") (pin "A") (pinfunction "A_A") (pintype "passive"))
      (node (ref "R11") (pin "2") (pinfunction "2_2") (pintype "passive"))
    )
    (net (code "30") (name "Net-(IC2-IN)") (class "Default")
      (node (ref "IC2") (pin "3") (pinfunction "IN_3") (pintype "input"))
      (node (ref "R5") (pin "2") (pinfunction "2_2") (pintype "passive"))
    )
    (net (code "31") (name "Net-(IC2-VO_N)") (class "Default")
      (node (ref "IC2") (pin "1") (pinfunction "VO_N_1") (pintype "output"))
      (node (ref "SP2") (pin "+") (pinfunction "+_+") (pintype "passive"))
    )
    (net (code "32") (name "Net-(IC2-VO_P)") (class "Default")
      (node (ref "IC2") (pin "6") (pinfunction "VO_P_6") (pintype "output"))
      (node (ref "SP2") (pin "-") (pinfunction "-_-") (pintype "passive"))
    )
    (net (code "33") (name "Net-(IC3-XIN)") (class "Default")
      (node (ref "C19") (pin "2") (pinfunction "2_2") (pintype "passive"))
      (node (ref "IC3") (pin "20") (pinfunction "XIN_20") (pintype "input"))
      (node (ref "Y1") (pin "3") (pinfunction "2_3") (pintype "passive"))
    )
    (net (code "34") (name "Net-(IC3-XOUT)") (class "Default")
      (node (ref "IC3") (pin "21") (pinfunction "XOUT_21") (pintype "output"))
      (node (ref "R6") (pin "2") (pinfunction "2_2") (pintype "passive"))
    )
    (net (code "35") (name "Net-(LED1-DO)") (class "Default")
      (node (ref "LED1") (pin "2-DOUT") (pinfunction "DO_2-DOUT") (pintype "output"))
      (node (ref "LED2") (pin "4-DIN") (pinfunction "DI_4-DIN") (pintype "input"))
    )
    (net (code "36") (name "Net-(LED2-DO)") (class "Default")
      (node (ref "LED2") (pin "2-DOUT") (pinfunction "DO_2-DOUT") (pintype "output"))
      (node (ref "LED3") (pin "4-DIN") (pinfunction "DI_4-DIN") (pintype "input"))
    )
    (net (code "37") (name "Net-(LED3-DO)") (class "Default")
      (node (ref "LED3") (pin "2-DOUT") (pinfunction "DO_2-DOUT") (pintype "output"))
      (node (ref "LED4") (pin "4-DIN") (pinfunction "DI_4-DIN") (pintype "input"))
    )
    (net (code "38") (name "Net-(LED4-DO)") (class "Default")
      (node (ref "LED4") (pin "2-DOUT") (pinfunction "DO_2-DOUT") (pintype "output"))
      (node (ref "LED5") (pin "4-DIN") (pinfunction "DI_4-DIN") (pintype "input"))
    )
    (net (code "39") (name "Net-(LED5-DO)") (class "Default")
      (node (ref "LED5") (pin "2-DOUT") (pinfunction "DO_2-DOUT") (pintype "output"))
      (node (ref "LED6") (pin "4-DIN") (pinfunction "DI_4-DIN") (pintype "input"))
    )
    (net (code "40") (name "Net-(LED6-DO)") (class "Default")
      (node (ref "LED6") (pin "2-DOUT") (pinfunction "DO_2-DOUT") (pintype "output"))
      (node (ref "LED7") (pin "4-DIN") (pinfunction "DI_4-DIN") (pintype "input"))
    )
    (net (code "41") (name "Net-(LED7-DO)") (class "Default")
      (node (ref "LED7") (pin "2-DOUT") (pinfunction "DO_2-DOUT") (pintype "output"))
      (node (ref "LED8") (pin "4-DIN") (pinfunction "DI_4-DIN") (pintype "input"))
    )
    (net (code "42") (name "Net-(LED8-DO)") (class "Default")
      (node (ref "LED8") (pin "2-DOUT") (pinfunction "DO_2-DOUT") (pintype "output"))
      (node (ref "LED9") (pin "4-DIN") (pinfunction "DI_4-DIN") (pintype "input"))
    )
    (net (code "43") (name "Net-(LED10-DI)") (class "Default")
      (node (ref "LED10") (pin "4-DIN") (pinfunction "DI_4-DIN") (pintype "input"))
      (node (ref "LED9") (pin "2-DOUT") (pinfunction "DO_2-DOUT") (pintype "output"))
    )
    (net (code "44") (name "Net-(LED10-DO)") (class "Default")
      (node (ref "LED10") (pin "2-DOUT") (pinfunction "DO_2-DOUT") (pintype "output"))
      (node (ref "LED11") (pin "4-DIN") (pinfunction "DI_4-DIN") (pintype "input"))
    )
    (net (code "45") (name "Net-(LED11-DO)") (class "Default")
      (node (ref "LED11") (pin "2-DOUT") (pinfunction "DO_2-DOUT") (pintype "output"))
      (node (ref "LED12") (pin "4-DIN") (pinfunction "DI_4-DIN") (pintype "input"))
    )
    (net (code "46") (name "Net-(R1A-2)") (class "Default")
      (node (ref "L") (pin "A") (pinfunction "A_A") (pintype "passive"))
      (node (ref "R1") (pin "8") (pinfunction "2_8") (pintype "passive"))
    )
    (net (code "47") (name "Net-(R3-Pad1)") (class "Default")
      (node (ref "R3") (pin "1") (pinfunction "1_1") (pintype "passive"))
      (node (ref "X1") (pin "A6") (pinfunction "D+_A6") (pintype "bidirectional"))
      (node (ref "X1") (pin "B6") (pinfunction "D+_B6") (pintype "bidirectional"))
    )
    (net (code "48") (name "Net-(R4-Pad1)") (class "Default")
      (node (ref "R4") (pin "1") (pinfunction "1_1") (pintype "passive"))
      (node (ref "X1") (pin "A7") (pinfunction "D-_A7") (pintype "bidirectional"))
      (node (ref "X1") (pin "B7") (pinfunction "D-_B7") (pintype "bidirectional"))
    )
    (net (code "49") (name "Net-(X2-C1+)") (class "Default")
      (node (ref "C15") (pin "2") (pinfunction "2_2") (pintype "passive"))
      (node (ref "X2") (pin "3") (pinfunction "C1+_3") (pintype "input"))
    )
    (net (code "50") (name "Net-(X2-C1-)") (class "Default")
      (node (ref "C15") (pin "1") (pinfunction "1_1") (pintype "passive"))
      (node (ref "X2") (pin "4") (pinfunction "C1-_4") (pintype "input"))
    )
    (net (code "51") (name "Net-(X2-C2+)") (class "Default")
      (node (ref "C17") (pin "2") (pinfunction "2_2") (pintype "passive"))
      (node (ref "X2") (pin "1") (pinfunction "C2+_1") (pintype "input"))
    )
    (net (code "52") (name "Net-(X2-C2-)") (class "Default")
      (node (ref "C17") (pin "1") (pinfunction "1_1") (pintype "passive"))
      (node (ref "X2") (pin "2") (pinfunction "C2-_2") (pintype "input"))
    )
    (net (code "53") (name "Net-(X2-IREF)") (class "Default")
      (node (ref "R12") (pin "2") (pinfunction "2_2") (pintype "passive"))
      (node (ref "X2") (pin "13") (pinfunction "IREF_13") (pintype "bidirectional"))
    )
    (net (code "54") (name "OLED_CS") (class "Default")
      (node (ref "IC3") (pin "34") (pinfunction "GPIO22_34") (pintype "bidirectional"))
      (node (ref "X2") (pin "8") (pinfunction "~{CS}_8") (pintype "input"))
    )
    (net (code "55") (name "OLED_DC") (class "Default")
      (node (ref "IC3") (pin "36") (pinfunction "GPIO24_36") (pintype "bidirectional"))
      (node (ref "X2") (pin "10") (pinfunction "D/~{C}_10") (pintype "input"))
    )
    (net (code "56") (name "OLED_RST") (class "Default")
      (node (ref "IC3") (pin "35") (pinfunction "GPIO23_35") (pintype "bidirectional"))
      (node (ref "R14") (pin "4") (pinfunction "1_4") (pintype "passive"))
      (node (ref "X2") (pin "9") (pinfunction "~{RES}_9") (pintype "input"))
    )
    (net (code "57") (name "QSPI_CS") (class "Default")
      (node (ref "IC3") (pin "56") (pinfunction "~{QSPI_CS}_56") (pintype "bidirectional"))
      (node (ref "R11") (pin "1") (pinfunction "1_1") (pintype "passive"))
      (node (ref "R2") (pin "2") (pinfunction "2_2") (pintype "passive"))
      (node (ref "TP6") (pin "P$1") (pinfunction "P$1_P$1") (pintype "bidirectional"))
      (node (ref "U1") (pin "1") (pinfunction "SSEL_1") (pintype "bidirectional"))
    )
    (net (code "58") (name "QSPI_DATA[0]") (class "Default")
      (node (ref "IC3") (pin "53") (pinfunction "QSPI_SD0_53") (pintype "bidirectional"))
      (node (ref "U1") (pin "5") (pinfunction "MOSI_5") (pintype "bidirectional"))
    )
    (net (code "59") (name "QSPI_DATA[1]") (class "Default")
      (node (ref "IC3") (pin "55") (pinfunction "QSPI_SD1_55") (pintype "bidirectional"))
      (node (ref "U1") (pin "2") (pinfunction "MISO_2") (pintype "bidirectional"))
    )
    (net (code "60") (name "QSPI_DATA[2]") (class "Default")
      (node (ref "IC3") (pin "54") (pinfunction "QSPI_SD2_54") (pintype "bidirectional"))
      (node (ref "U1") (pin "3") (pinfunction "WP#/IO2_3") (pintype "bidirectional"))
    )
    (net (code "61") (name "QSPI_DATA[3]") (class "Default")
      (node (ref "IC3") (pin "51") (pinfunction "QSPI_SD3_51") (pintype "bidirectional"))
      (node (ref "U1") (pin "7") (pinfunction "HOLD#/IO3_7") (pintype "bidirectional"))
    )
    (net (code "62") (name "QSPI_SCK") (class "Default")
      (node (ref "IC3") (pin "52") (pinfunction "QSPI_SCLK_52") (pintype "bidirectional"))
      (node (ref "U1") (pin "6") (pinfunction "SCK_6") (pintype "bidirectional"))
    )
    (net (code "63") (name "ROTA") (class "Default")
      (node (ref "IC3") (pin "28") (pinfunction "GPIO17_28") (pintype "bidirectional"))
      (node (ref "SW1") (pin "P$A") (pinfunction "P$A_P$A") (pintype "passive"))
    )
    (net (code "64") (name "ROTB") (class "Default")
      (node (ref "IC3") (pin "29") (pinfunction "GPIO18_29") (pintype "bidirectional"))
      (node (ref "SW1") (pin "P$B") (pinfunction "P$B_P$B") (pintype "passive"))
    )
    (net (code "65") (name "SCK") (class "Default")
      (node (ref "IC3") (pin "38") (pinfunction "GPIO26/AD0_38") (pintype "bidirectional"))
      (node (ref "X2") (pin "11") (pinfunction "SCK_11") (pintype "input"))
    )
    (net (code "66") (name "SCL") (class "Default")
      (node (ref "CONN1") (pin "4") (pinfunction "SCL_4") (pintype "passive"))
      (node (ref "IC3") (pin "32") (pinfunction "GPIO21_32") (pintype "bidirectional"))
      (node (ref "R14") (pin "3") (pinfunction "1_3") (pintype "passive"))
    )
    (net (code "67") (name "SDA") (class "Default")
      (node (ref "CONN1") (pin "3") (pinfunction "SDA_3") (pintype "passive"))
      (node (ref "IC3") (pin "31") (pinfunction "GPIO20_31") (pintype "bidirectional"))
      (node (ref "R14") (pin "2") (pinfunction "1_2") (pintype "passive"))
    )
    (net (code "68") (name "SPEAKER") (class "Default")
      (node (ref "IC3") (pin "27") (pinfunction "GPIO16_27") (pintype "bidirectional"))
      (node (ref "R8") (pin "1") (pinfunction "1_1") (pintype "passive"))
    )
    (net (code "69") (name "SPKR_SD") (class "Default")
      (node (ref "IC2") (pin "4") (pinfunction "/SD_4") (pintype "input"))
      (node (ref "IC3") (pin "17") (pinfunction "GPIO14_17") (pintype "bidirectional"))
      (node (ref "R10") (pin "1") (pinfunction "1_1") (pintype "passive"))
    )
    (net (code "70") (name "USBBOOT") (class "Default")
      (node (ref "D3") (pin "C") (pinfunction "C_C") (pintype "passive"))
      (node (ref "IC3") (pin "2") (pinfunction "GPIO0_2") (pintype "bidirectional"))
      (node (ref "SW1") (pin "P$1") (pinfunction "P$1_P$1") (pintype "passive"))
    )
    (net (code "71") (name "VCC") (class "Default")
      (node (ref "C14") (pin "2") (pinfunction "2_2") (pintype "passive"))
      (node (ref "X2") (pin "15") (pinfunction "VCC_15") (pintype "power_in"))
    )
    (net (code "72") (name "VCOMH") (class "Default")
      (node (ref "C9") (pin "2") (pinfunction "2_2") (pintype "passive"))
      (node (ref "X2") (pin "14") (pinfunction "VCOMH_14") (pintype "power_in"))
    )
    (net (code "73") (name "unconnected-(IC3-GPIO15-Pad18)") (class "Default")
      (node (ref "IC3") (pin "18") (pinfunction "GPIO15_18") (pintype "bidirectional"))
    )
    (net (code "74") (name "unconnected-(IC3-GPIO25-Pad37)") (class "Default")
      (node (ref "IC3") (pin "37") (pinfunction "GPIO25_37") (pintype "bidirectional"))
    )
    (net (code "75") (name "unconnected-(IC3-GPIO29{slash}AD3-Pad41)") (class "Default")
      (node (ref "IC3") (pin "41") (pinfunction "GPIO29/AD3_41") (pintype "bidirectional"))
    )
    (net (code "76") (name "unconnected-(IC3-SWCLK-Pad24)") (class "Default")
      (node (ref "IC3") (pin "24") (pinfunction "SWCLK_24") (pintype "bidirectional"))
    )
    (net (code "77") (name "unconnected-(IC3-SWDIO-Pad25)") (class "Default")
      (node (ref "IC3") (pin "25") (pinfunction "SWDIO_25") (pintype "bidirectional"))
    )
    (net (code "78") (name "unconnected-(LED12-DO-Pad2-DOUT)") (class "Default")
      (node (ref "LED12") (pin "2-DOUT") (pinfunction "DO_2-DOUT") (pintype "output"))
    )
    (net (code "79") (name "unconnected-(TP1-SEW-PadP$1)") (class "Default")
      (node (ref "TP1") (pin "P$1") (pinfunction "SEW_P$1") (pintype "bidirectional"))
    )
    (net (code "80") (name "unconnected-(TP2-SEW-PadP$1)") (class "Default")
      (node (ref "TP2") (pin "P$1") (pinfunction "SEW_P$1") (pintype "bidirectional"))
    )
    (net (code "81") (name "unconnected-(TP3-SEW-PadP$1)") (class "Default")
      (node (ref "TP3") (pin "P$1") (pinfunction "SEW_P$1") (pintype "bidirectional"))
    )
    (net (code "82") (name "unconnected-(TP4-SEW-PadP$1)") (class "Default")
      (node (ref "TP4") (pin "P$1") (pinfunction "SEW_P$1") (pintype "bidirectional"))
    )
    (net (code "83") (name "unconnected-(U2-P4-Pad4)") (class "Default")
      (node (ref "U2") (pin "4") (pinfunction "P4_4") (pintype "bidirectional"))
    )
    (net (code "84") (name "unconnected-(X1-SBU1-PadA8)") (class "Default")
      (node (ref "X1") (pin "A8") (pinfunction "SBU1_A8") (pintype "bidirectional"))
    )
    (net (code "85") (name "unconnected-(X1-SBU2-PadB8)") (class "Default")
      (node (ref "X1") (pin "B8") (pinfunction "SBU2_B8") (pintype "bidirectional"))
    )
    (net (code "86") (name "~{RESET}") (class "Default")
      (node (ref "IC3") (pin "26") (pinfunction "/RUN_26") (pintype "bidirectional"))
      (node (ref "R14") (pin "1") (pinfunction "1_1") (pintype "passive"))
      (node (ref "SW2") (pin "2") (pinfunction "S_2") (pintype "passive"))
      (node (ref "TP5") (pin "P$1") (pinfunction "P$1_P$1") (pintype "bidirectional"))
    )
  )
)
